# Dimmer_Circuit.net
KiCad netlist of a schematic drawn in EAGLE
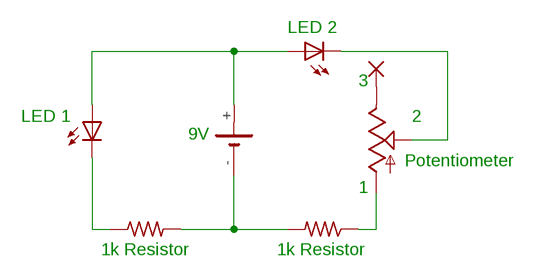
[diagram p0: schematic, sheet 1]

(export (version "E")
  (design (tool "Eeschema 10.0.6"))
  (components
    (comp (ref "G1")
      (value "SL-150-1/2AA/PR")
      (footprint "eagle-import:SL-150-1_2AA_PR")
      (libsource (lib "eagle-import") (part "SL-150-1/2AA/PR"))
    )
    (comp (ref "LED1")
      (value "LAP4-BOTTOM")
      (footprint "eagle-import:P47F-BOTTOM")
      (libsource (lib "eagle-import") (part "P4-BOTTOMLA"))
    )
    (comp (ref "LED2")
      (value "LAP4-BOTTOM")
      (footprint "eagle-import:P47F-BOTTOM")
      (libsource (lib "eagle-import") (part "P4-BOTTOMLA"))
    )
    (comp (ref "PAD1")
      (value "2,15/1,0")
      (footprint "eagle-import:2,15_1,0")
      (libsource (lib "eagle-import") (part "2,15/1,0"))
    )
    (comp (ref "R1")
      (value "R-US_0204/2V")
      (footprint "eagle-import:0204V")
      (libsource (lib "eagle-import") (part "R-US_0204/2V"))
    )
    (comp (ref "R2")
      (value "R-US_0204/2V")
      (footprint "eagle-import:0204V")
      (libsource (lib "eagle-import") (part "R-US_0204/2V"))
    )
    (comp (ref "R3")
      (value "TRIM_US-ECP10S")
      (footprint "eagle-import:ECP10S")
      (libsource (lib "eagle-import") (part "TRIM_US-ECP10S"))
    )
  )
  (nets
    (net (code "1") (name "Net-(G1-Pad+)") (class "Default")
      (node (ref "G1") (pin "+") (pinfunction "+_+") (pintype "passive"))
      (node (ref "LED1") (pin "A") (pinfunction "A_A") (pintype "passive"))
      (node (ref "LED2") (pin "A") (pinfunction "A_A") (pintype "passive"))
    )
    (net (code "2") (name "Net-(G1-Pad-)") (class "Default")
      (node (ref "G1") (pin "-") (pinfunction "-_-") (pintype "passive"))
      (node (ref "R1") (pin "2") (pinfunction "2_2") (pintype "passive"))
      (node (ref "R2") (pin "2") (pinfunction "2_2") (pintype "passive"))
    )
    (net (code "3") (name "Net-(LED1-PadC)") (class "Default")
      (node (ref "LED1") (pin "C") (pinfunction "C_C") (pintype "passive"))
      (node (ref "R2") (pin "1") (pinfunction "1_1") (pintype "passive"))
    )
    (net (code "4") (name "Net-(LED2-PadC)") (class "Default")
      (node (ref "LED2") (pin "C") (pinfunction "C_C") (pintype "passive"))
      (node (ref "R3") (pin "S") (pinfunction "S_S") (pintype "passive"))
    )
    (net (code "5") (name "Net-(PAD1-P)") (class "Default")
      (node (ref "PAD1") (pin "1") (pinfunction "P_1") (pintype "passive"))
      (node (ref "R3") (pin "E") (pinfunction "E_E") (pintype "passive"))
    )
    (net (code "6") (name "Net-(R1-Pad1)") (class "Default")
      (node (ref "R1") (pin "1") (pinfunction "1_1") (pintype "passive"))
      (node (ref "R3") (pin "A") (pinfunction "A_A") (pintype "passive"))
    )
  )
)
